# WL_PGA_ATT.net
KiCad netlist of a schematic drawn in Altium Designer
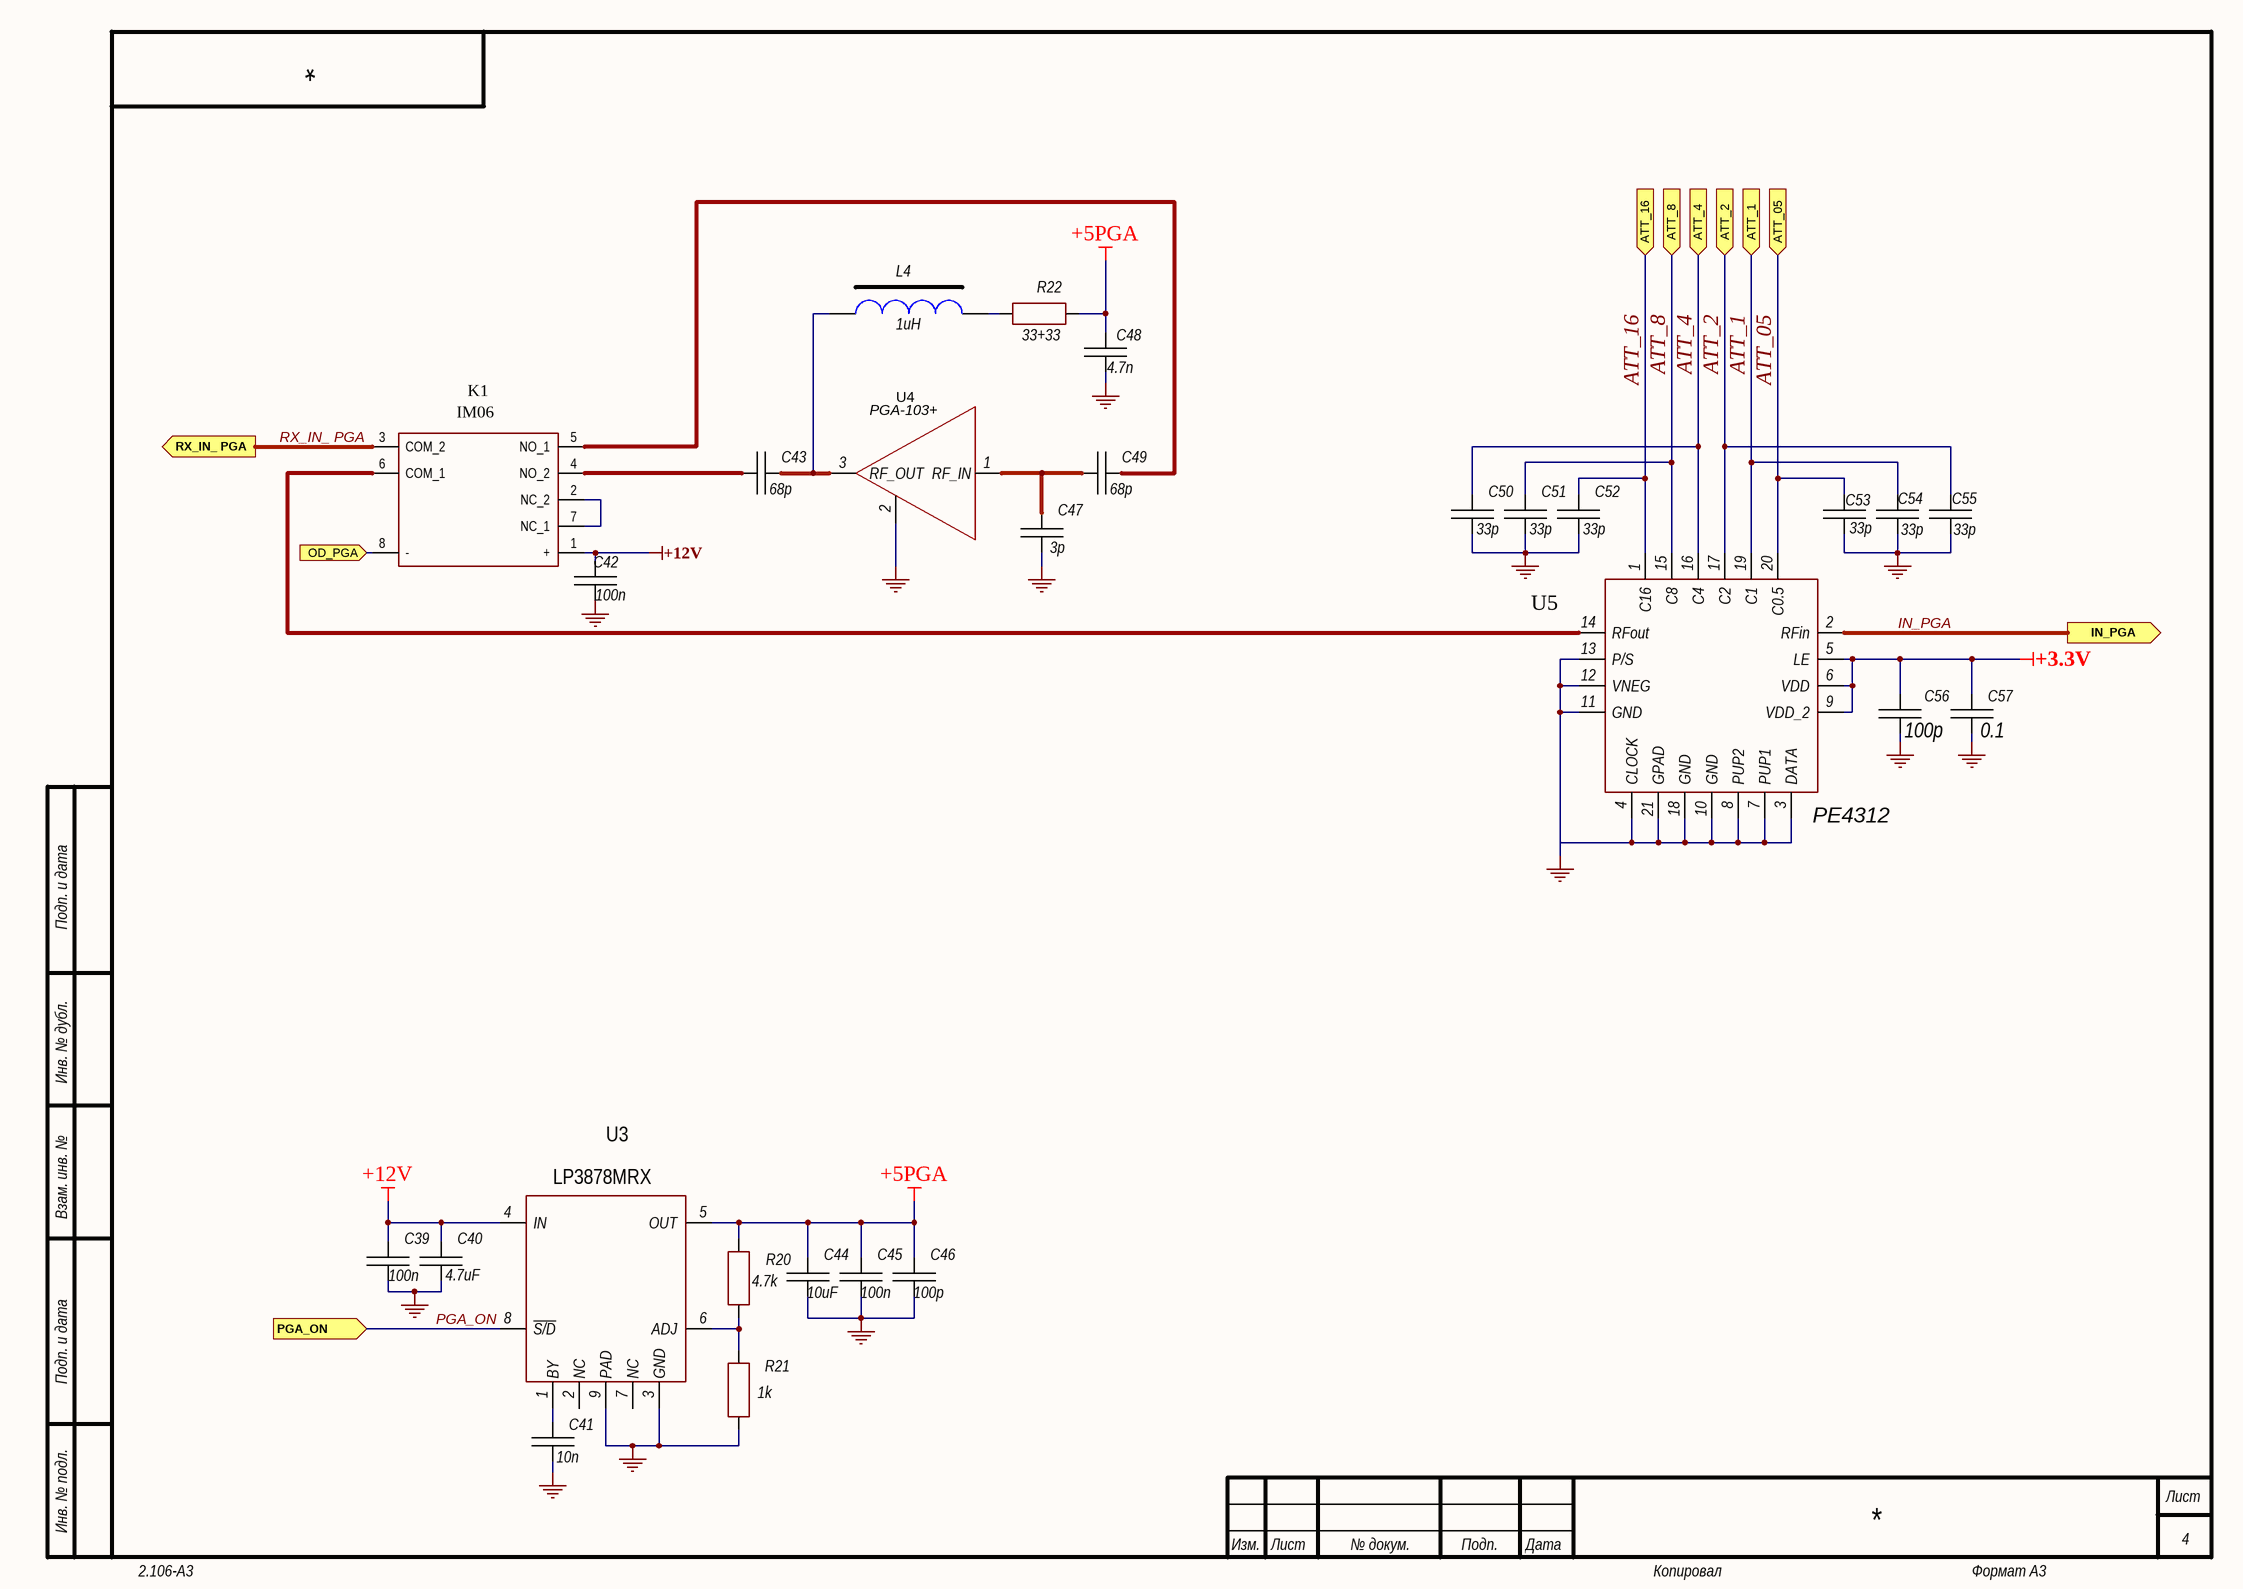
[diagram p0: WL_PGA_ATT.SchDoc]

(export (version "E")
  (design (tool "Eeschema 10.0.6"))
  (components
    (comp (ref "C39")
      (value "100n")
      (footprint "standard:CH0805C")
      (libsource (lib "Discrete") (part "Capacitor"))
    )
    (comp (ref "C40")
      (value "4.7uF")
      (footprint "standard:CH0805C")
      (libsource (lib "Discrete") (part "Capacitor"))
    )
    (comp (ref "C41")
      (value "10n")
      (footprint "standard:CH0805C")
      (libsource (lib "Discrete") (part "Capacitor"))
    )
    (comp (ref "C42")
      (value "100n")
      (footprint "standard:CH0805C")
      (libsource (lib "Discrete") (part "Capacitor"))
    )
    (comp (ref "C43")
      (value "68p")
      (footprint "standard:CH0805C")
      (libsource (lib "Discrete") (part "Capacitor"))
    )
    (comp (ref "C44")
      (value "10uF")
      (footprint "standard:CH0805C")
      (libsource (lib "Discrete") (part "Capacitor"))
    )
    (comp (ref "C45")
      (value "100n")
      (footprint "standard:CH0805C")
      (libsource (lib "Discrete") (part "Capacitor"))
    )
    (comp (ref "C46")
      (value "100p")
      (footprint "standard:CH0805C")
      (libsource (lib "Discrete") (part "Capacitor"))
    )
    (comp (ref "C47")
      (value "3p")
      (footprint "standard:CH0805C")
      (libsource (lib "Discrete") (part "Capacitor"))
    )
    (comp (ref "C48")
      (value "4.7n")
      (footprint "standard:CH0805C")
      (libsource (lib "Discrete") (part "Capacitor"))
    )
    (comp (ref "C49")
      (value "68p")
      (footprint "standard:CH0805C")
      (libsource (lib "Discrete") (part "Capacitor"))
    )
    (comp (ref "C50")
      (value "33p")
      (footprint "standard:CH0603C")
      (libsource (lib "Discrete") (part "Capacitor"))
    )
    (comp (ref "C51")
      (value "33p")
      (footprint "standard:CH0603C")
      (libsource (lib "Discrete") (part "Capacitor"))
    )
    (comp (ref "C52")
      (value "33p")
      (footprint "standard:CH0603C")
      (libsource (lib "Discrete") (part "Capacitor"))
    )
    (comp (ref "C53")
      (value "33p")
      (footprint "standard:CH0603C")
      (libsource (lib "Discrete") (part "Capacitor"))
    )
    (comp (ref "C54")
      (value "33p")
      (footprint "standard:CH0603C")
      (libsource (lib "Discrete") (part "Capacitor"))
    )
    (comp (ref "C55")
      (value "33p")
      (footprint "standard:CH0603C")
      (libsource (lib "Discrete") (part "Capacitor"))
    )
    (comp (ref "C56")
      (value "100p")
      (footprint "standard:CH0805C")
      (libsource (lib "Discrete") (part "Capacitor"))
    )
    (comp (ref "C57")
      (value "0.1")
      (footprint "standard:CH0805C")
      (libsource (lib "Discrete") (part "Capacitor"))
    )
    (comp (ref "K1") (value "IM06") (footprint "IM06") (libsource (lib "Relay") (part "IM06-V1")))
    (comp (ref "L4") (value "1uH") (footprint "L1210") (libsource (lib "Transformers") (part "TRANS")))
    (comp (ref "R20")
      (value "4.7k")
      (footprint "standard:CH0805R")
      (libsource (lib "Discrete") (part "Resistor"))
    )
    (comp (ref "R21")
      (value "1k")
      (footprint "standard:CH0805R")
      (libsource (lib "Discrete") (part "Resistor"))
    )
    (comp (ref "R22") (value "33+33") (footprint "WL_RFFC:CH1206R") (libsource (lib "") (part "Resistor_1")))
    (comp (ref "U3")
      (value "LP3878MRX")
      (footprint "8-SOIC (PAD)")
      (libsource (lib "Power Supplies") (part "LP3878"))
    )
    (comp (ref "U4") (value "PGA-103+") (footprint "SOT89_123") (libsource (lib "Digital") (part "PGA-103+")))
    (comp (ref "U5") (value "PE4312") (footprint "20-QFN (4x4)") (libsource (lib "Digital") (part "PE4302")))
  )
  (nets
    (net (code "1") (name "+3.3V") (class "Default")
      (node (ref "C56") (pin "1") (pinfunction "1_1") (pintype "passive"))
      (node (ref "C57") (pin "1") (pinfunction "1_1") (pintype "passive"))
      (node (ref "U5") (pin "5") (pinfunction "LE_5") (pintype "passive"))
      (node (ref "U5") (pin "6") (pinfunction "VDD_6") (pintype "passive"))
      (node (ref "U5") (pin "9") (pinfunction "VDD_2_9") (pintype "passive"))
    )
    (net (code "2") (name "+5PGA") (class "Default")
      (node (ref "C44") (pin "2") (pinfunction "2_2") (pintype "passive"))
      (node (ref "C45") (pin "2") (pinfunction "2_2") (pintype "passive"))
      (node (ref "C46") (pin "2") (pinfunction "2_2") (pintype "passive"))
      (node (ref "C48") (pin "2") (pinfunction "2_2") (pintype "passive"))
      (node (ref "R20") (pin "2") (pinfunction "2_2") (pintype "passive"))
      (node (ref "R22") (pin "2") (pinfunction "2_2") (pintype "passive"))
      (node (ref "U3") (pin "5") (pinfunction "OUT_5") (pintype "power_in"))
    )
    (net (code "3") (name "+12V") (class "Default")
      (node (ref "C39") (pin "2") (pinfunction "2_2") (pintype "passive"))
      (node (ref "C40") (pin "2") (pinfunction "2_2") (pintype "passive"))
      (node (ref "C42") (pin "2") (pinfunction "2_2") (pintype "passive"))
      (node (ref "K1") (pin "1") (pinfunction "+_1") (pintype "passive"))
      (node (ref "U3") (pin "4") (pinfunction "IN_4") (pintype "power_in"))
    )
    (net (code "4") (name "/ATT_1") (class "Default")
      (node (ref "C54") (pin "2") (pinfunction "2_2") (pintype "passive"))
      (node (ref "U5") (pin "19") (pinfunction "C1_19") (pintype "passive"))
    )
    (net (code "5") (name "/ATT_2") (class "Default")
      (node (ref "C55") (pin "2") (pinfunction "2_2") (pintype "passive"))
      (node (ref "U5") (pin "17") (pinfunction "C2_17") (pintype "passive"))
    )
    (net (code "6") (name "/ATT_4") (class "Default")
      (node (ref "C50") (pin "2") (pinfunction "2_2") (pintype "passive"))
      (node (ref "U5") (pin "16") (pinfunction "C4_16") (pintype "passive"))
    )
    (net (code "7") (name "/ATT_05") (class "Default")
      (node (ref "C53") (pin "2") (pinfunction "2_2") (pintype "passive"))
      (node (ref "U5") (pin "20") (pinfunction "C0.5_20") (pintype "passive"))
    )
    (net (code "8") (name "/ATT_8") (class "Default")
      (node (ref "C51") (pin "2") (pinfunction "2_2") (pintype "passive"))
      (node (ref "U5") (pin "15") (pinfunction "C8_15") (pintype "passive"))
    )
    (net (code "9") (name "/ATT_16") (class "Default")
      (node (ref "C52") (pin "2") (pinfunction "2_2") (pintype "passive"))
      (node (ref "U5") (pin "1") (pinfunction "C16_1") (pintype "passive"))
    )
    (net (code "10") (name "/IN_PGA") (class "Default")
      (node (ref "U5") (pin "2") (pinfunction "RFin_2") (pintype "passive"))
    )
    (net (code "11") (name "/OD_PGA") (class "Default")
      (node (ref "K1") (pin "8") (pinfunction "-_8") (pintype "passive"))
    )
    (net (code "12") (name "/PGA_ON") (class "Default")
      (node (ref "U3") (pin "8") (pinfunction "~{S/D}_8") (pintype "power_in"))
    )
    (net (code "13") (name "/RX_IN_ PGA") (class "Default")
      (node (ref "K1") (pin "3") (pinfunction "COM_2_3") (pintype "passive"))
    )
    (net (code "14") (name "GND") (class "Default")
      (node (ref "C39") (pin "1") (pinfunction "1_1") (pintype "passive"))
      (node (ref "C40") (pin "1") (pinfunction "1_1") (pintype "passive"))
      (node (ref "C41") (pin "1") (pinfunction "1_1") (pintype "passive"))
      (node (ref "C42") (pin "1") (pinfunction "1_1") (pintype "passive"))
      (node (ref "C44") (pin "1") (pinfunction "1_1") (pintype "passive"))
      (node (ref "C45") (pin "1") (pinfunction "1_1") (pintype "passive"))
      (node (ref "C46") (pin "1") (pinfunction "1_1") (pintype "passive"))
      (node (ref "C47") (pin "1") (pinfunction "1_1") (pintype "passive"))
      (node (ref "C48") (pin "1") (pinfunction "1_1") (pintype "passive"))
      (node (ref "C50") (pin "1") (pinfunction "1_1") (pintype "passive"))
      (node (ref "C51") (pin "1") (pinfunction "1_1") (pintype "passive"))
      (node (ref "C52") (pin "1") (pinfunction "1_1") (pintype "passive"))
      (node (ref "C53") (pin "1") (pinfunction "1_1") (pintype "passive"))
      (node (ref "C54") (pin "1") (pinfunction "1_1") (pintype "passive"))
      (node (ref "C55") (pin "1") (pinfunction "1_1") (pintype "passive"))
      (node (ref "C56") (pin "2") (pinfunction "2_2") (pintype "passive"))
      (node (ref "C57") (pin "2") (pinfunction "2_2") (pintype "passive"))
      (node (ref "R21") (pin "1") (pinfunction "1_1") (pintype "passive"))
      (node (ref "U3") (pin "3") (pinfunction "GND_3") (pintype "passive"))
      (node (ref "U3") (pin "9") (pinfunction "PAD_9") (pintype "passive"))
      (node (ref "U4") (pin "2") (pinfunction "GND_2") (pintype "passive"))
      (node (ref "U5") (pin "10") (pinfunction "GND_10") (pintype "passive"))
      (node (ref "U5") (pin "11") (pinfunction "GND_11") (pintype "passive"))
      (node (ref "U5") (pin "12") (pinfunction "VNEG_12") (pintype "passive"))
      (node (ref "U5") (pin "13") (pinfunction "P/S_13") (pintype "passive"))
      (node (ref "U5") (pin "18") (pinfunction "GND_18") (pintype "passive"))
      (node (ref "U5") (pin "21") (pinfunction "GPAD_21") (pintype "passive"))
      (node (ref "U5") (pin "3") (pinfunction "DATA_3") (pintype "passive"))
      (node (ref "U5") (pin "4") (pinfunction "CLOCK_4") (pintype "passive"))
      (node (ref "U5") (pin "7") (pinfunction "PUP1_7") (pintype "passive"))
      (node (ref "U5") (pin "8") (pinfunction "PUP2_8") (pintype "passive"))
    )
    (net (code "15") (name "Net-(K1-COM_1)") (class "Default")
      (node (ref "K1") (pin "6") (pinfunction "COM_1_6") (pintype "passive"))
      (node (ref "U5") (pin "14") (pinfunction "RFout_14") (pintype "passive"))
    )
    (net (code "16") (name "Net-(K1-NC_1)") (class "Default")
      (node (ref "K1") (pin "2") (pinfunction "NC_2_2") (pintype "passive"))
      (node (ref "K1") (pin "7") (pinfunction "NC_1_7") (pintype "passive"))
    )
    (net (code "17") (name "Net-(K1-NO_1)") (class "Default")
      (node (ref "C49") (pin "2") (pinfunction "2_2") (pintype "passive"))
      (node (ref "K1") (pin "5") (pinfunction "NO_1_5") (pintype "passive"))
    )
    (net (code "18") (name "Net-(K1-NO_2)") (class "Default")
      (node (ref "C43") (pin "1") (pinfunction "1_1") (pintype "passive"))
      (node (ref "K1") (pin "4") (pinfunction "NO_2_4") (pintype "passive"))
    )
    (net (code "19") (name "Net-(L4-Pad1)") (class "Default")
      (node (ref "L4") (pin "1") (pinfunction "1_1") (pintype "power_in"))
      (node (ref "R22") (pin "1") (pinfunction "1_1") (pintype "passive"))
    )
    (net (code "20") (name "Net-(U3-ADJ)") (class "Default")
      (node (ref "R20") (pin "1") (pinfunction "1_1") (pintype "passive"))
      (node (ref "R21") (pin "2") (pinfunction "2_2") (pintype "passive"))
      (node (ref "U3") (pin "6") (pinfunction "ADJ_6") (pintype "passive"))
    )
    (net (code "21") (name "Net-(U3-BY)") (class "Default")
      (node (ref "C41") (pin "2") (pinfunction "2_2") (pintype "passive"))
      (node (ref "U3") (pin "1") (pinfunction "BY_1") (pintype "passive"))
    )
    (net (code "22") (name "Net-(U4-RF_IN)") (class "Default")
      (node (ref "C47") (pin "2") (pinfunction "2_2") (pintype "passive"))
      (node (ref "C49") (pin "1") (pinfunction "1_1") (pintype "passive"))
      (node (ref "U4") (pin "1") (pinfunction "RF_IN_1") (pintype "passive"))
    )
    (net (code "23") (name "Net-(U4-RF_OUT)") (class "Default")
      (node (ref "C43") (pin "2") (pinfunction "2_2") (pintype "passive"))
      (node (ref "L4") (pin "2") (pinfunction "2_2") (pintype "power_in"))
      (node (ref "U4") (pin "3") (pinfunction "RF_OUT_3") (pintype "passive"))
    )
    (net (code "24") (name "unconnected-(U3-NC-Pad2)") (class "Default")
      (node (ref "U3") (pin "2") (pinfunction "NC_2") (pintype "passive"))
    )
    (net (code "25") (name "unconnected-(U3-NC-Pad7)") (class "Default")
      (node (ref "U3") (pin "7") (pinfunction "NC_7") (pintype "passive"))
    )
  )
)
